# Photodiode_plate.net
KiCad netlist of a schematic drawn in EasyEDA
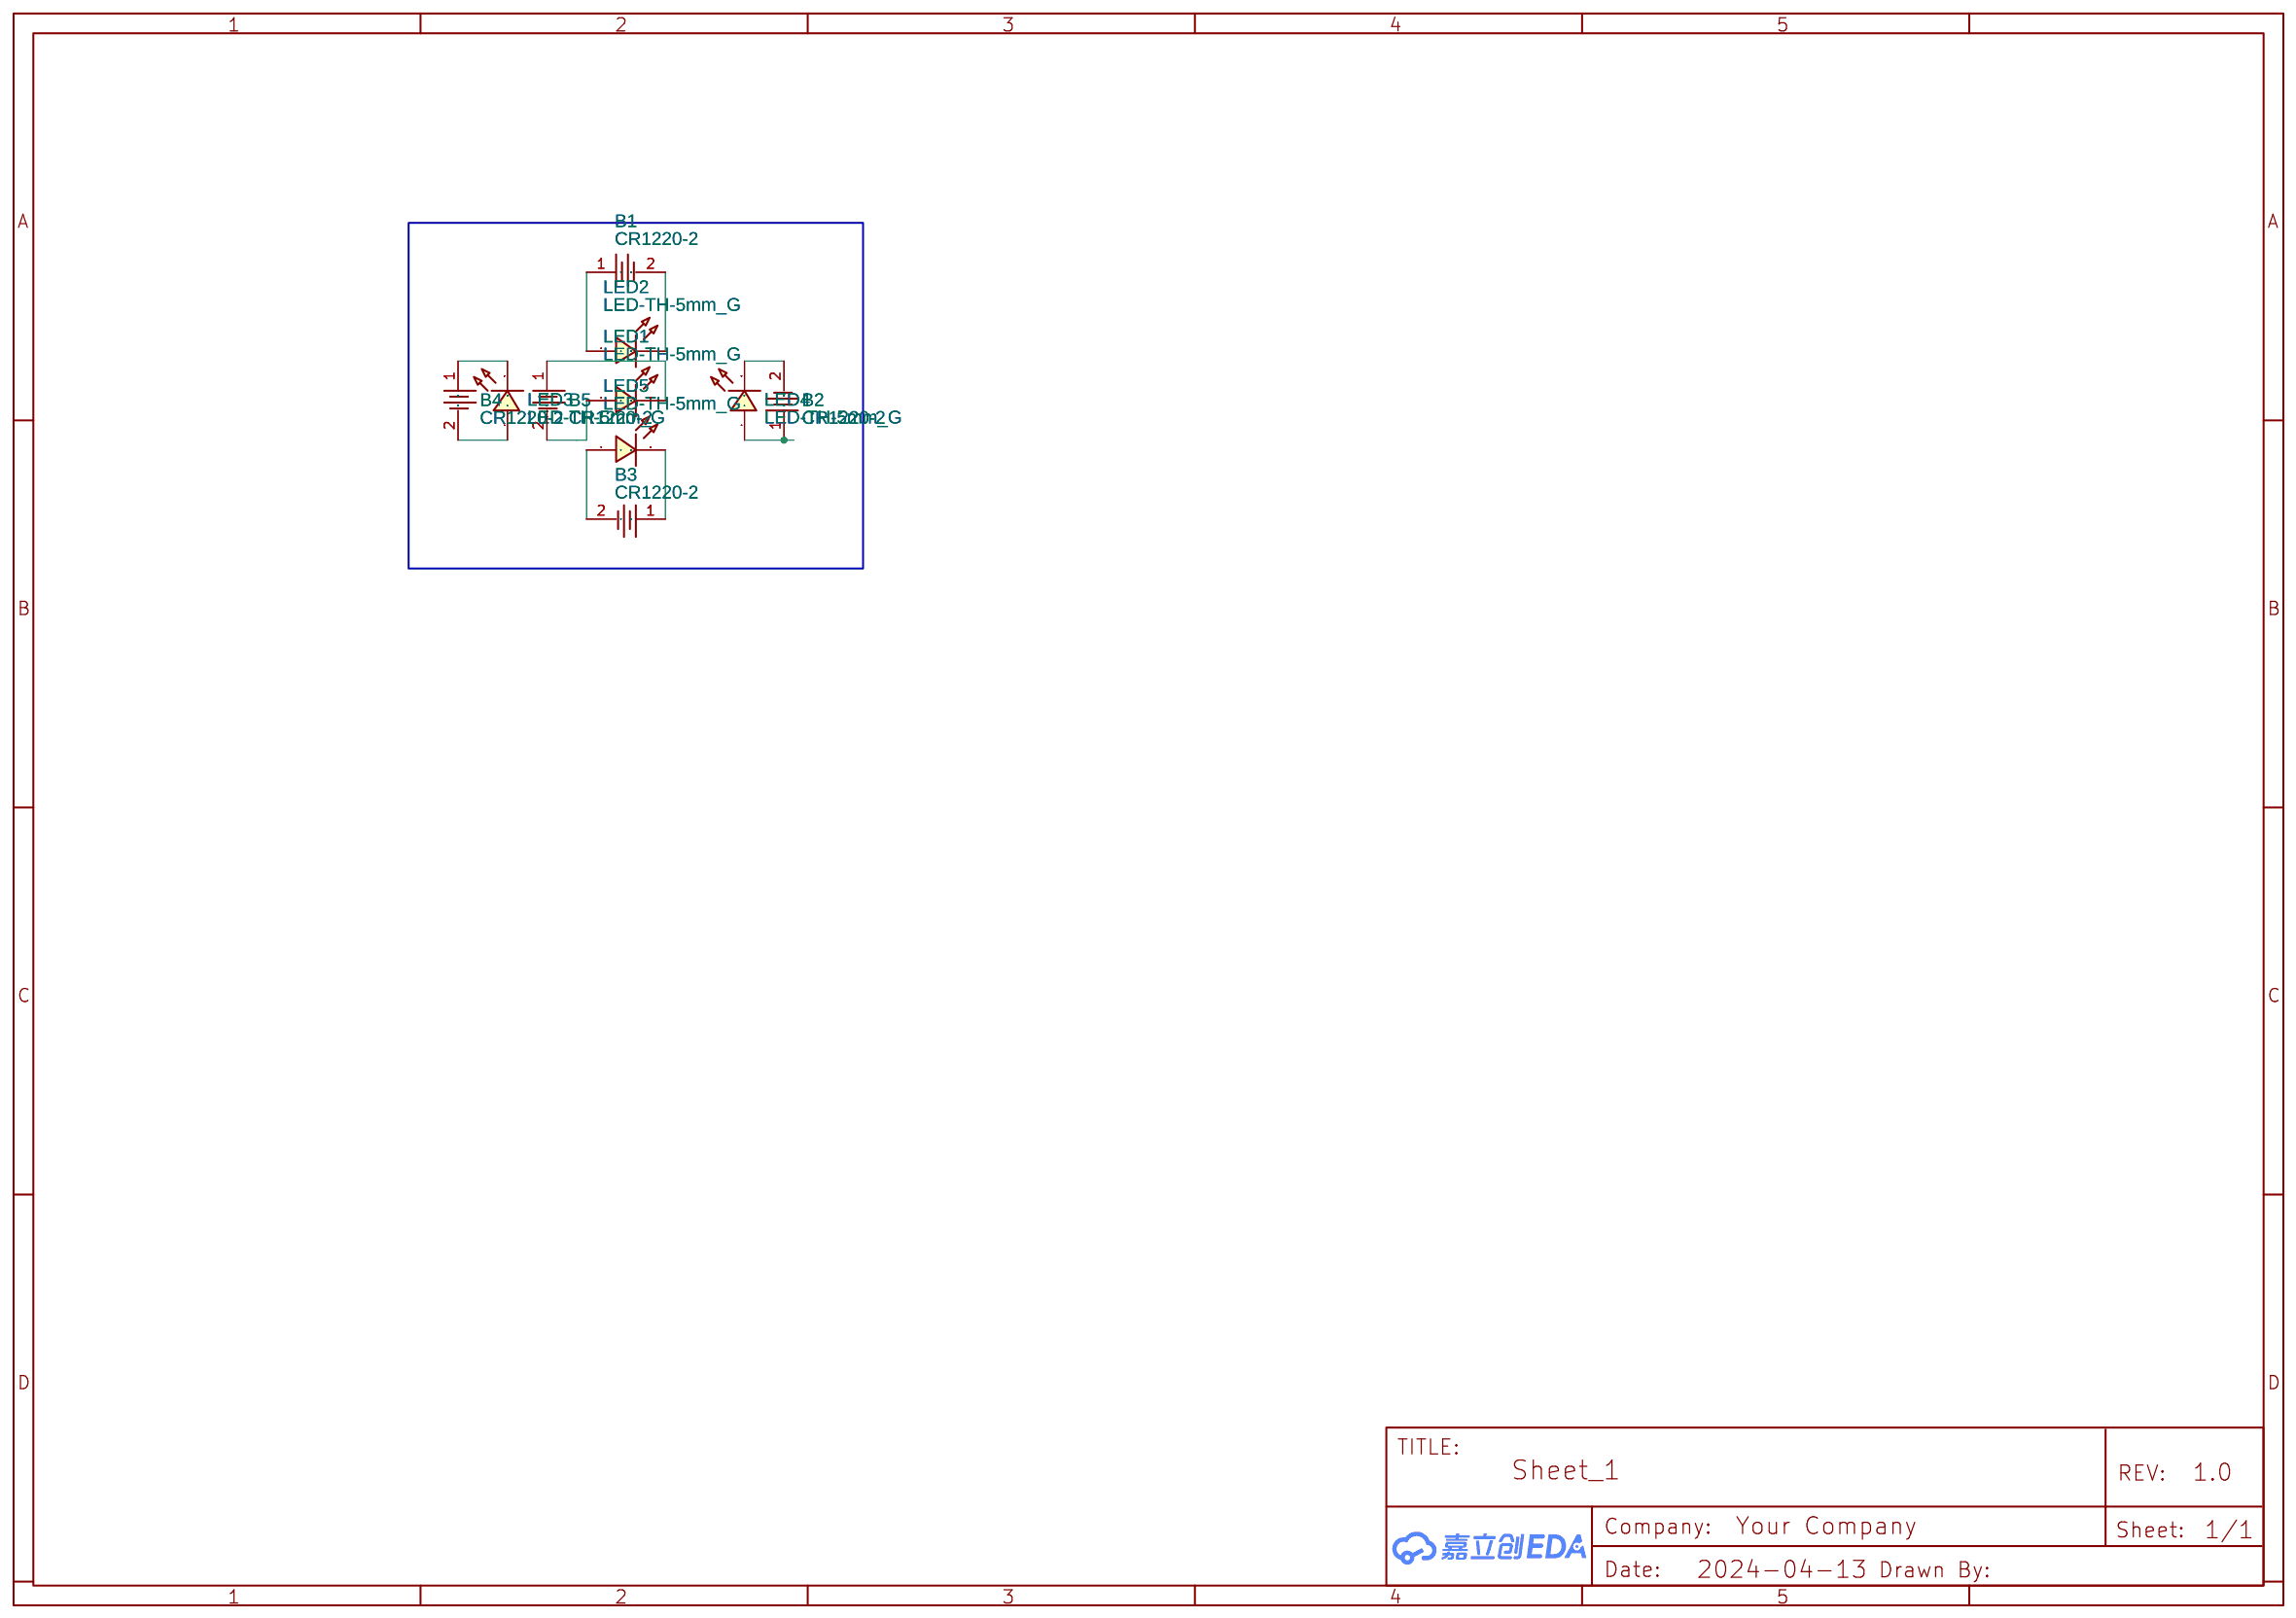
[diagram p0: schematic sheet]

(export (version "E")
  (design (tool "Eeschema 10.0.6"))
  (components
    (comp (ref "B1")
      (value "CR1220-2")
      (fields (field (name "BOM_Supplier Part") "C70381"))
      (libsource (lib "") (part "CR1220-2_3"))
    )
    (comp (ref "B2")
      (value "CR1220-2")
      (fields (field (name "BOM_Supplier Part") "C70381"))
      (libsource (lib "") (part "CR1220-2"))
    )
    (comp (ref "B3")
      (value "CR1220-2")
      (fields (field (name "BOM_Supplier Part") "C70381"))
      (libsource (lib "") (part "CR1220-2_1"))
    )
    (comp (ref "B4")
      (value "CR1220-2")
      (fields (field (name "BOM_Supplier Part") "C70381"))
      (libsource (lib "") (part "CR1220-2_2"))
    )
    (comp (ref "B5")
      (value "CR1220-2")
      (fields (field (name "BOM_Supplier Part") "C70381"))
      (libsource (lib "") (part "CR1220-2_2"))
    )
    (comp (ref "LED1")
      (value "LED-TH-5mm_G")
      (fields
        (field (name "BOM_Manufacturer Part") "333-2SYGD/S530-E2")
        (field (name "BOM_Supplier Part") "C88163")
      )
      (libsource (lib "") (part "LED-TH-5mm_G"))
    )
    (comp (ref "LED2")
      (value "LED-TH-5mm_G")
      (fields
        (field (name "BOM_Manufacturer Part") "333-2SYGD/S530-E2")
        (field (name "BOM_Supplier Part") "C88163")
      )
      (libsource (lib "") (part "LED-TH-5mm_G"))
    )
    (comp (ref "LED3")
      (value "LED-TH-5mm_G")
      (fields
        (field (name "BOM_Manufacturer Part") "333-2SYGD/S530-E2")
        (field (name "BOM_Supplier Part") "C88163")
      )
      (libsource (lib "") (part "LED-TH-5mm_G_1"))
    )
    (comp (ref "LED4")
      (value "LED-TH-5mm_G")
      (fields
        (field (name "BOM_Manufacturer Part") "333-2SYGD/S530-E2")
        (field (name "BOM_Supplier Part") "C88163")
      )
      (libsource (lib "") (part "LED-TH-5mm_G_1"))
    )
    (comp (ref "LED5")
      (value "LED-TH-5mm_G")
      (fields
        (field (name "BOM_Manufacturer Part") "333-2SYGD/S530-E2")
        (field (name "BOM_Supplier Part") "C88163")
      )
      (libsource (lib "") (part "LED-TH-5mm_G"))
    )
  )
  (nets
    (net (code "1") (name "Net-(B1-Pad1)") (class "Default")
      (node (ref "B1") (pin "1") (pinfunction "1_1") (pintype "input"))
      (node (ref "LED2") (pin "1") (pinfunction "1_1") (pintype "unspecified"))
    )
    (net (code "2") (name "Net-(B1-Pad2)") (class "Default")
      (node (ref "B1") (pin "2") (pinfunction "2_2") (pintype "input"))
      (node (ref "LED2") (pin "2") (pinfunction "2_2") (pintype "unspecified"))
    )
    (net (code "3") (name "Net-(B2-Pad1)") (class "Default")
      (node (ref "B2") (pin "1") (pinfunction "1_1") (pintype "input"))
      (node (ref "LED4") (pin "1") (pinfunction "1_1") (pintype "unspecified"))
    )
    (net (code "4") (name "Net-(B2-Pad2)") (class "Default")
      (node (ref "B2") (pin "2") (pinfunction "2_2") (pintype "input"))
      (node (ref "LED4") (pin "2") (pinfunction "2_2") (pintype "unspecified"))
    )
    (net (code "5") (name "Net-(B3-Pad1)") (class "Default")
      (node (ref "B3") (pin "1") (pinfunction "1_1") (pintype "input"))
      (node (ref "LED5") (pin "2") (pinfunction "2_2") (pintype "unspecified"))
    )
    (net (code "6") (name "Net-(B3-Pad2)") (class "Default")
      (node (ref "B3") (pin "2") (pinfunction "2_2") (pintype "input"))
      (node (ref "LED5") (pin "1") (pinfunction "1_1") (pintype "unspecified"))
    )
    (net (code "7") (name "Net-(B4-Pad1)") (class "Default")
      (node (ref "B4") (pin "1") (pinfunction "1_1") (pintype "input"))
      (node (ref "LED3") (pin "2") (pinfunction "2_2") (pintype "unspecified"))
    )
    (net (code "8") (name "Net-(B4-Pad2)") (class "Default")
      (node (ref "B4") (pin "2") (pinfunction "2_2") (pintype "input"))
      (node (ref "LED3") (pin "1") (pinfunction "1_1") (pintype "unspecified"))
    )
    (net (code "9") (name "Net-(B5-Pad1)") (class "Default")
      (node (ref "B5") (pin "1") (pinfunction "1_1") (pintype "input"))
      (node (ref "LED1") (pin "2") (pinfunction "2_2") (pintype "unspecified"))
    )
    (net (code "10") (name "Net-(B5-Pad2)") (class "Default")
      (node (ref "B5") (pin "2") (pinfunction "2_2") (pintype "input"))
      (node (ref "LED1") (pin "1") (pinfunction "1_1") (pintype "unspecified"))
    )
  )
)
